# FET_M2.net
KiCad netlist of a schematic drawn in Altium Designer
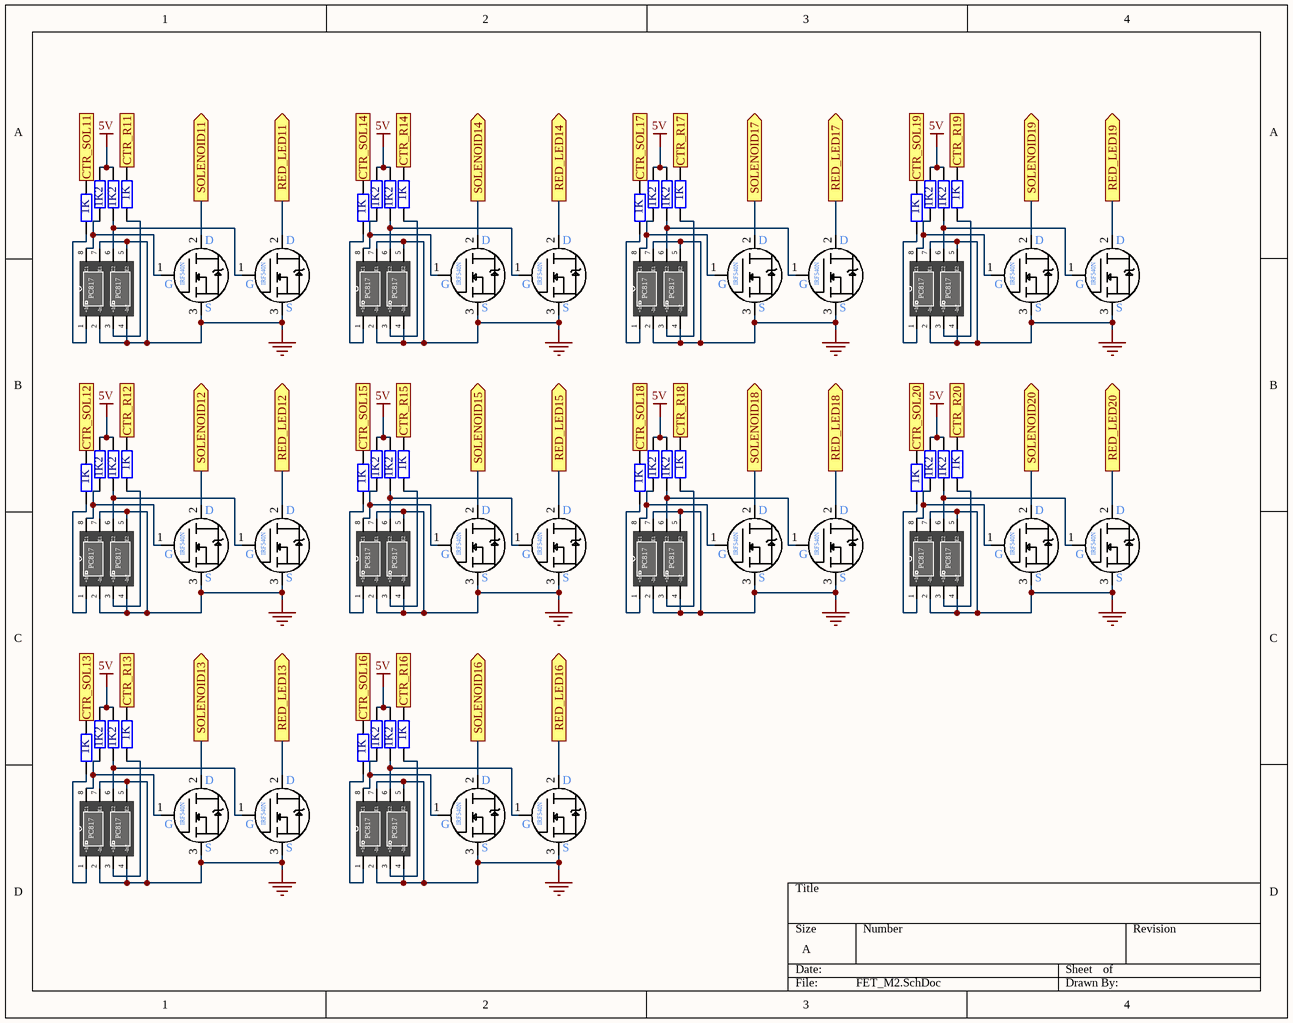
[diagram p0: FET_M2.SchDoc]

(export (version "E")
  (design (tool "Eeschema 10.0.6"))
  (components
    (comp (ref "FET21")
      (value "5#IRF540N")
      (footprint "5#IRF540N")
      (libsource (lib "Sch") (part "5#IRF540N"))
    )
    (comp (ref "FET22")
      (value "5#IRF540N")
      (footprint "5#IRF540N")
      (libsource (lib "Sch") (part "5#IRF540N"))
    )
    (comp (ref "FET23")
      (value "5#IRF540N")
      (footprint "5#IRF540N")
      (libsource (lib "Sch") (part "5#IRF540N"))
    )
    (comp (ref "FET24")
      (value "5#IRF540N")
      (footprint "5#IRF540N")
      (libsource (lib "Sch") (part "5#IRF540N"))
    )
    (comp (ref "FET25")
      (value "5#IRF540N")
      (footprint "5#IRF540N")
      (libsource (lib "Sch") (part "5#IRF540N"))
    )
    (comp (ref "FET26")
      (value "5#IRF540N")
      (footprint "5#IRF540N")
      (libsource (lib "Sch") (part "5#IRF540N"))
    )
    (comp (ref "FET27")
      (value "5#IRF540N")
      (footprint "5#IRF540N")
      (libsource (lib "Sch") (part "5#IRF540N"))
    )
    (comp (ref "FET28")
      (value "5#IRF540N")
      (footprint "5#IRF540N")
      (libsource (lib "Sch") (part "5#IRF540N"))
    )
    (comp (ref "FET29")
      (value "5#IRF540N")
      (footprint "5#IRF540N")
      (libsource (lib "Sch") (part "5#IRF540N"))
    )
    (comp (ref "FET30")
      (value "5#IRF540N")
      (footprint "5#IRF540N")
      (libsource (lib "Sch") (part "5#IRF540N"))
    )
    (comp (ref "FET31")
      (value "5#IRF540N")
      (footprint "5#IRF540N")
      (libsource (lib "Sch") (part "5#IRF540N"))
    )
    (comp (ref "FET32")
      (value "5#IRF540N")
      (footprint "5#IRF540N")
      (libsource (lib "Sch") (part "5#IRF540N"))
    )
    (comp (ref "FET33")
      (value "5#IRF540N")
      (footprint "5#IRF540N")
      (libsource (lib "Sch") (part "5#IRF540N"))
    )
    (comp (ref "FET34")
      (value "5#IRF540N")
      (footprint "5#IRF540N")
      (libsource (lib "Sch") (part "5#IRF540N"))
    )
    (comp (ref "FET35")
      (value "5#IRF540N")
      (footprint "5#IRF540N")
      (libsource (lib "Sch") (part "5#IRF540N"))
    )
    (comp (ref "FET36")
      (value "5#IRF540N")
      (footprint "5#IRF540N")
      (libsource (lib "Sch") (part "5#IRF540N"))
    )
    (comp (ref "FET37")
      (value "5#IRF540N")
      (footprint "5#IRF540N")
      (libsource (lib "Sch") (part "5#IRF540N"))
    )
    (comp (ref "FET38")
      (value "5#IRF540N")
      (footprint "5#IRF540N")
      (libsource (lib "Sch") (part "5#IRF540N"))
    )
    (comp (ref "FET39")
      (value "5#IRF540N")
      (footprint "5#IRF540N")
      (libsource (lib "Sch") (part "5#IRF540N"))
    )
    (comp (ref "FET40")
      (value "5#IRF540N")
      (footprint "5#IRF540N")
      (libsource (lib "Sch") (part "5#IRF540N"))
    )
    (comp (ref "PC11")
      (value "5#Dip8_PC817x2")
      (footprint "5#Dip8_PC817x2")
      (libsource (lib "Sch") (part "5#Dip8_PC817x2"))
    )
    (comp (ref "PC12")
      (value "5#Dip8_PC817x2")
      (footprint "5#Dip8_PC817x2")
      (libsource (lib "Sch") (part "5#Dip8_PC817x2"))
    )
    (comp (ref "PC13")
      (value "5#Dip8_PC817x2")
      (footprint "5#Dip8_PC817x2")
      (libsource (lib "Sch") (part "5#Dip8_PC817x2"))
    )
    (comp (ref "PC14")
      (value "5#Dip8_PC817x2")
      (footprint "5#Dip8_PC817x2")
      (libsource (lib "Sch") (part "5#Dip8_PC817x2"))
    )
    (comp (ref "PC15")
      (value "5#Dip8_PC817x2")
      (footprint "5#Dip8_PC817x2")
      (libsource (lib "Sch") (part "5#Dip8_PC817x2"))
    )
    (comp (ref "PC16")
      (value "5#Dip8_PC817x2")
      (footprint "5#Dip8_PC817x2")
      (libsource (lib "Sch") (part "5#Dip8_PC817x2"))
    )
    (comp (ref "PC17")
      (value "5#Dip8_PC817x2")
      (footprint "5#Dip8_PC817x2")
      (libsource (lib "Sch") (part "5#Dip8_PC817x2"))
    )
    (comp (ref "PC18")
      (value "5#Dip8_PC817x2")
      (footprint "5#Dip8_PC817x2")
      (libsource (lib "Sch") (part "5#Dip8_PC817x2"))
    )
    (comp (ref "PC19")
      (value "5#Dip8_PC817x2")
      (footprint "5#Dip8_PC817x2")
      (libsource (lib "Sch") (part "5#Dip8_PC817x2"))
    )
    (comp (ref "PC20")
      (value "5#Dip8_PC817x2")
      (footprint "5#Dip8_PC817x2")
      (libsource (lib "Sch") (part "5#Dip8_PC817x2"))
    )
    (comp (ref "R66")
      (value "1K2")
      (footprint "AXIAL-0.4")
      (description "Resistor")
      (fields (field (name "PUBLISHER") "Altium Limited"))
      (libsource (lib "Miscellaneous Devices") (part "Res2"))
    )
    (comp (ref "R67")
      (value "1K2")
      (footprint "AXIAL-0.4")
      (description "Resistor")
      (fields (field (name "PUBLISHER") "Altium Limited"))
      (libsource (lib "Miscellaneous Devices") (part "Res2"))
    )
    (comp (ref "R68")
      (value "1K")
      (footprint "AXIAL-0.4")
      (description "Resistor")
      (fields (field (name "PUBLISHER") "Altium Limited"))
      (libsource (lib "") (part "Res2_1"))
    )
    (comp (ref "R69")
      (value "1K2")
      (footprint "AXIAL-0.4")
      (description "Resistor")
      (fields (field (name "PUBLISHER") "Altium Limited"))
      (libsource (lib "Miscellaneous Devices") (part "Res2"))
    )
    (comp (ref "R70")
      (value "1K2")
      (footprint "AXIAL-0.4")
      (description "Resistor")
      (fields (field (name "PUBLISHER") "Altium Limited"))
      (libsource (lib "Miscellaneous Devices") (part "Res2"))
    )
    (comp (ref "R71")
      (value "1K")
      (footprint "AXIAL-0.4")
      (description "Resistor")
      (fields (field (name "PUBLISHER") "Altium Limited"))
      (libsource (lib "") (part "Res2_1"))
    )
    (comp (ref "R72")
      (value "1K2")
      (footprint "AXIAL-0.4")
      (description "Resistor")
      (fields (field (name "PUBLISHER") "Altium Limited"))
      (libsource (lib "Miscellaneous Devices") (part "Res2"))
    )
    (comp (ref "R73")
      (value "1K2")
      (footprint "AXIAL-0.4")
      (description "Resistor")
      (fields (field (name "PUBLISHER") "Altium Limited"))
      (libsource (lib "Miscellaneous Devices") (part "Res2"))
    )
    (comp (ref "R74")
      (value "1K")
      (footprint "AXIAL-0.4")
      (description "Resistor")
      (fields (field (name "PUBLISHER") "Altium Limited"))
      (libsource (lib "") (part "Res2_1"))
    )
    (comp (ref "R75")
      (value "1K2")
      (footprint "AXIAL-0.4")
      (description "Resistor")
      (fields (field (name "PUBLISHER") "Altium Limited"))
      (libsource (lib "Miscellaneous Devices") (part "Res2"))
    )
    (comp (ref "R76")
      (value "1K2")
      (footprint "AXIAL-0.4")
      (description "Resistor")
      (fields (field (name "PUBLISHER") "Altium Limited"))
      (libsource (lib "Miscellaneous Devices") (part "Res2"))
    )
    (comp (ref "R77")
      (value "1K")
      (footprint "AXIAL-0.4")
      (description "Resistor")
      (fields (field (name "PUBLISHER") "Altium Limited"))
      (libsource (lib "") (part "Res2_1"))
    )
    (comp (ref "R78")
      (value "1K")
      (footprint "AXIAL-0.4")
      (description "Resistor")
      (fields (field (name "PUBLISHER") "Altium Limited"))
      (libsource (lib "") (part "Res2_1"))
    )
    (comp (ref "R79")
      (value "1K")
      (footprint "AXIAL-0.4")
      (description "Resistor")
      (fields (field (name "PUBLISHER") "Altium Limited"))
      (libsource (lib "") (part "Res2_1"))
    )
    (comp (ref "R80")
      (value "1K")
      (footprint "AXIAL-0.4")
      (description "Resistor")
      (fields (field (name "PUBLISHER") "Altium Limited"))
      (libsource (lib "") (part "Res2_1"))
    )
    (comp (ref "R81")
      (value "1K")
      (footprint "AXIAL-0.4")
      (description "Resistor")
      (fields (field (name "PUBLISHER") "Altium Limited"))
      (libsource (lib "") (part "Res2_1"))
    )
    (comp (ref "R82")
      (value "1K2")
      (footprint "AXIAL-0.4")
      (description "Resistor")
      (fields (field (name "PUBLISHER") "Altium Limited"))
      (libsource (lib "Miscellaneous Devices") (part "Res2"))
    )
    (comp (ref "R83")
      (value "1K2")
      (footprint "AXIAL-0.4")
      (description "Resistor")
      (fields (field (name "PUBLISHER") "Altium Limited"))
      (libsource (lib "Miscellaneous Devices") (part "Res2"))
    )
    (comp (ref "R84")
      (value "1K")
      (footprint "AXIAL-0.4")
      (description "Resistor")
      (fields (field (name "PUBLISHER") "Altium Limited"))
      (libsource (lib "") (part "Res2_1"))
    )
    (comp (ref "R85")
      (value "1K2")
      (footprint "AXIAL-0.4")
      (description "Resistor")
      (fields (field (name "PUBLISHER") "Altium Limited"))
      (libsource (lib "Miscellaneous Devices") (part "Res2"))
    )
    (comp (ref "R86")
      (value "1K2")
      (footprint "AXIAL-0.4")
      (description "Resistor")
      (fields (field (name "PUBLISHER") "Altium Limited"))
      (libsource (lib "Miscellaneous Devices") (part "Res2"))
    )
    (comp (ref "R87")
      (value "1K")
      (footprint "AXIAL-0.4")
      (description "Resistor")
      (fields (field (name "PUBLISHER") "Altium Limited"))
      (libsource (lib "") (part "Res2_1"))
    )
    (comp (ref "R88")
      (value "1K2")
      (footprint "AXIAL-0.4")
      (description "Resistor")
      (fields (field (name "PUBLISHER") "Altium Limited"))
      (libsource (lib "Miscellaneous Devices") (part "Res2"))
    )
    (comp (ref "R89")
      (value "1K2")
      (footprint "AXIAL-0.4")
      (description "Resistor")
      (fields (field (name "PUBLISHER") "Altium Limited"))
      (libsource (lib "Miscellaneous Devices") (part "Res2"))
    )
    (comp (ref "R90")
      (value "1K")
      (footprint "AXIAL-0.4")
      (description "Resistor")
      (fields (field (name "PUBLISHER") "Altium Limited"))
      (libsource (lib "") (part "Res2_1"))
    )
    (comp (ref "R91")
      (value "1K2")
      (footprint "AXIAL-0.4")
      (description "Resistor")
      (fields (field (name "PUBLISHER") "Altium Limited"))
      (libsource (lib "Miscellaneous Devices") (part "Res2"))
    )
    (comp (ref "R92")
      (value "1K2")
      (footprint "AXIAL-0.4")
      (description "Resistor")
      (fields (field (name "PUBLISHER") "Altium Limited"))
      (libsource (lib "Miscellaneous Devices") (part "Res2"))
    )
    (comp (ref "R93")
      (value "1K")
      (footprint "AXIAL-0.4")
      (description "Resistor")
      (fields (field (name "PUBLISHER") "Altium Limited"))
      (libsource (lib "") (part "Res2_1"))
    )
    (comp (ref "R94")
      (value "1K")
      (footprint "AXIAL-0.4")
      (description "Resistor")
      (fields (field (name "PUBLISHER") "Altium Limited"))
      (libsource (lib "") (part "Res2_1"))
    )
    (comp (ref "R95")
      (value "1K")
      (footprint "AXIAL-0.4")
      (description "Resistor")
      (fields (field (name "PUBLISHER") "Altium Limited"))
      (libsource (lib "") (part "Res2_1"))
    )
    (comp (ref "R96")
      (value "1K")
      (footprint "AXIAL-0.4")
      (description "Resistor")
      (fields (field (name "PUBLISHER") "Altium Limited"))
      (libsource (lib "") (part "Res2_1"))
    )
    (comp (ref "R97")
      (value "1K")
      (footprint "AXIAL-0.4")
      (description "Resistor")
      (fields (field (name "PUBLISHER") "Altium Limited"))
      (libsource (lib "") (part "Res2_1"))
    )
    (comp (ref "R98")
      (value "1K2")
      (footprint "AXIAL-0.4")
      (description "Resistor")
      (fields (field (name "PUBLISHER") "Altium Limited"))
      (libsource (lib "Miscellaneous Devices") (part "Res2"))
    )
    (comp (ref "R99")
      (value "1K2")
      (footprint "AXIAL-0.4")
      (description "Resistor")
      (fields (field (name "PUBLISHER") "Altium Limited"))
      (libsource (lib "Miscellaneous Devices") (part "Res2"))
    )
    (comp (ref "R100")
      (value "1K")
      (footprint "AXIAL-0.4")
      (description "Resistor")
      (fields (field (name "PUBLISHER") "Altium Limited"))
      (libsource (lib "") (part "Res2_1"))
    )
    (comp (ref "R101")
      (value "1K2")
      (footprint "AXIAL-0.4")
      (description "Resistor")
      (fields (field (name "PUBLISHER") "Altium Limited"))
      (libsource (lib "Miscellaneous Devices") (part "Res2"))
    )
    (comp (ref "R102")
      (value "1K2")
      (footprint "AXIAL-0.4")
      (description "Resistor")
      (fields (field (name "PUBLISHER") "Altium Limited"))
      (libsource (lib "Miscellaneous Devices") (part "Res2"))
    )
    (comp (ref "R103")
      (value "1K")
      (footprint "AXIAL-0.4")
      (description "Resistor")
      (fields (field (name "PUBLISHER") "Altium Limited"))
      (libsource (lib "") (part "Res2_1"))
    )
    (comp (ref "R104")
      (value "1K")
      (footprint "AXIAL-0.4")
      (description "Resistor")
      (fields (field (name "PUBLISHER") "Altium Limited"))
      (libsource (lib "") (part "Res2_1"))
    )
    (comp (ref "R105")
      (value "1K")
      (footprint "AXIAL-0.4")
      (description "Resistor")
      (fields (field (name "PUBLISHER") "Altium Limited"))
      (libsource (lib "") (part "Res2_1"))
    )
  )
  (nets
    (net (code "1") (name "/CTR_R11") (class "Default")
      (node (ref "R68") (pin "1") (pinfunction "1_1") (pintype "passive"))
    )
    (net (code "2") (name "/CTR_R12") (class "Default")
      (node (ref "R84") (pin "1") (pinfunction "1_1") (pintype "passive"))
    )
    (net (code "3") (name "/CTR_R13") (class "Default")
      (node (ref "R100") (pin "1") (pinfunction "1_1") (pintype "passive"))
    )
    (net (code "4") (name "/CTR_R14") (class "Default")
      (node (ref "R71") (pin "1") (pinfunction "1_1") (pintype "passive"))
    )
    (net (code "5") (name "/CTR_R15") (class "Default")
      (node (ref "R87") (pin "1") (pinfunction "1_1") (pintype "passive"))
    )
    (net (code "6") (name "/CTR_R16") (class "Default")
      (node (ref "R103") (pin "1") (pinfunction "1_1") (pintype "passive"))
    )
    (net (code "7") (name "/CTR_R17") (class "Default")
      (node (ref "R74") (pin "1") (pinfunction "1_1") (pintype "passive"))
    )
    (net (code "8") (name "/CTR_R18") (class "Default")
      (node (ref "R90") (pin "1") (pinfunction "1_1") (pintype "passive"))
    )
    (net (code "9") (name "/CTR_R19") (class "Default")
      (node (ref "R77") (pin "1") (pinfunction "1_1") (pintype "passive"))
    )
    (net (code "10") (name "/CTR_R20") (class "Default")
      (node (ref "R93") (pin "1") (pinfunction "1_1") (pintype "passive"))
    )
    (net (code "11") (name "/CTR_SOL11") (class "Default")
      (node (ref "R78") (pin "1") (pinfunction "1_1") (pintype "passive"))
    )
    (net (code "12") (name "/CTR_SOL12") (class "Default")
      (node (ref "R94") (pin "1") (pinfunction "1_1") (pintype "passive"))
    )
    (net (code "13") (name "/CTR_SOL13") (class "Default")
      (node (ref "R104") (pin "1") (pinfunction "1_1") (pintype "passive"))
    )
    (net (code "14") (name "/CTR_SOL14") (class "Default")
      (node (ref "R79") (pin "1") (pinfunction "1_1") (pintype "passive"))
    )
    (net (code "15") (name "/CTR_SOL15") (class "Default")
      (node (ref "R95") (pin "1") (pinfunction "1_1") (pintype "passive"))
    )
    (net (code "16") (name "/CTR_SOL16") (class "Default")
      (node (ref "R105") (pin "1") (pinfunction "1_1") (pintype "passive"))
    )
    (net (code "17") (name "/CTR_SOL17") (class "Default")
      (node (ref "R80") (pin "1") (pinfunction "1_1") (pintype "passive"))
    )
    (net (code "18") (name "/CTR_SOL18") (class "Default")
      (node (ref "R96") (pin "1") (pinfunction "1_1") (pintype "passive"))
    )
    (net (code "19") (name "/CTR_SOL19") (class "Default")
      (node (ref "R81") (pin "1") (pinfunction "1_1") (pintype "passive"))
    )
    (net (code "20") (name "/CTR_SOL20") (class "Default")
      (node (ref "R97") (pin "1") (pinfunction "1_1") (pintype "passive"))
    )
    (net (code "21") (name "/RED_LED11") (class "Default")
      (node (ref "FET22") (pin "2") (pinfunction "D_2") (pintype "passive"))
    )
    (net (code "22") (name "/RED_LED12") (class "Default")
      (node (ref "FET30") (pin "2") (pinfunction "D_2") (pintype "passive"))
    )
    (net (code "23") (name "/RED_LED13") (class "Default")
      (node (ref "FET38") (pin "2") (pinfunction "D_2") (pintype "passive"))
    )
    (net (code "24") (name "/RED_LED14") (class "Default")
      (node (ref "FET24") (pin "2") (pinfunction "D_2") (pintype "passive"))
    )
    (net (code "25") (name "/RED_LED15") (class "Default")
      (node (ref "FET32") (pin "2") (pinfunction "D_2") (pintype "passive"))
    )
    (net (code "26") (name "/RED_LED16") (class "Default")
      (node (ref "FET40") (pin "2") (pinfunction "D_2") (pintype "passive"))
    )
    (net (code "27") (name "/RED_LED17") (class "Default")
      (node (ref "FET26") (pin "2") (pinfunction "D_2") (pintype "passive"))
    )
    (net (code "28") (name "/RED_LED18") (class "Default")
      (node (ref "FET34") (pin "2") (pinfunction "D_2") (pintype "passive"))
    )
    (net (code "29") (name "/RED_LED19") (class "Default")
      (node (ref "FET28") (pin "2") (pinfunction "D_2") (pintype "passive"))
    )
    (net (code "30") (name "/RED_LED20") (class "Default")
      (node (ref "FET36") (pin "2") (pinfunction "D_2") (pintype "passive"))
    )
    (net (code "31") (name "/SOLENOID11") (class "Default")
      (node (ref "FET21") (pin "2") (pinfunction "D_2") (pintype "passive"))
    )
    (net (code "32") (name "/SOLENOID12") (class "Default")
      (node (ref "FET29") (pin "2") (pinfunction "D_2") (pintype "passive"))
    )
    (net (code "33") (name "/SOLENOID13") (class "Default")
      (node (ref "FET37") (pin "2") (pinfunction "D_2") (pintype "passive"))
    )
    (net (code "34") (name "/SOLENOID14") (class "Default")
      (node (ref "FET23") (pin "2") (pinfunction "D_2") (pintype "passive"))
    )
    (net (code "35") (name "/SOLENOID15") (class "Default")
      (node (ref "FET31") (pin "2") (pinfunction "D_2") (pintype "passive"))
    )
    (net (code "36") (name "/SOLENOID16") (class "Default")
      (node (ref "FET39") (pin "2") (pinfunction "D_2") (pintype "passive"))
    )
    (net (code "37") (name "/SOLENOID17") (class "Default")
      (node (ref "FET25") (pin "2") (pinfunction "D_2") (pintype "passive"))
    )
    (net (code "38") (name "/SOLENOID18") (class "Default")
      (node (ref "FET33") (pin "2") (pinfunction "D_2") (pintype "passive"))
    )
    (net (code "39") (name "/SOLENOID19") (class "Default")
      (node (ref "FET27") (pin "2") (pinfunction "D_2") (pintype "passive"))
    )
    (net (code "40") (name "/SOLENOID20") (class "Default")
      (node (ref "FET35") (pin "2") (pinfunction "D_2") (pintype "passive"))
    )
    (net (code "41") (name "5V") (class "Default")
      (node (ref "R101") (pin "2") (pinfunction "2_2") (pintype "passive"))
      (node (ref "R102") (pin "2") (pinfunction "2_2") (pintype "passive"))
      (node (ref "R66") (pin "2") (pinfunction "2_2") (pintype "passive"))
      (node (ref "R67") (pin "2") (pinfunction "2_2") (pintype "passive"))
      (node (ref "R69") (pin "2") (pinfunction "2_2") (pintype "passive"))
      (node (ref "R70") (pin "2") (pinfunction "2_2") (pintype "passive"))
      (node (ref "R72") (pin "2") (pinfunction "2_2") (pintype "passive"))
      (node (ref "R73") (pin "2") (pinfunction "2_2") (pintype "passive"))
      (node (ref "R75") (pin "2") (pinfunction "2_2") (pintype "passive"))
      (node (ref "R76") (pin "2") (pinfunction "2_2") (pintype "passive"))
      (node (ref "R82") (pin "2") (pinfunction "2_2") (pintype "passive"))
      (node (ref "R83") (pin "2") (pinfunction "2_2") (pintype "passive"))
      (node (ref "R85") (pin "2") (pinfunction "2_2") (pintype "passive"))
      (node (ref "R86") (pin "2") (pinfunction "2_2") (pintype "passive"))
      (node (ref "R88") (pin "2") (pinfunction "2_2") (pintype "passive"))
      (node (ref "R89") (pin "2") (pinfunction "2_2") (pintype "passive"))
      (node (ref "R91") (pin "2") (pinfunction "2_2") (pintype "passive"))
      (node (ref "R92") (pin "2") (pinfunction "2_2") (pintype "passive"))
      (node (ref "R98") (pin "2") (pinfunction "2_2") (pintype "passive"))
      (node (ref "R99") (pin "2") (pinfunction "2_2") (pintype "passive"))
    )
    (net (code "42") (name "GND") (class "Default")
      (node (ref "FET21") (pin "3") (pinfunction "S_3") (pintype "passive"))
      (node (ref "FET22") (pin "3") (pinfunction "S_3") (pintype "passive"))
      (node (ref "FET23") (pin "3") (pinfunction "S_3") (pintype "passive"))
      (node (ref "FET24") (pin "3") (pinfunction "S_3") (pintype "passive"))
      (node (ref "FET25") (pin "3") (pinfunction "S_3") (pintype "passive"))
      (node (ref "FET26") (pin "3") (pinfunction "S_3") (pintype "passive"))
      (node (ref "FET27") (pin "3") (pinfunction "S_3") (pintype "passive"))
      (node (ref "FET28") (pin "3") (pinfunction "S_3") (pintype "passive"))
      (node (ref "FET29") (pin "3") (pinfunction "S_3") (pintype "passive"))
      (node (ref "FET30") (pin "3") (pinfunction "S_3") (pintype "passive"))
      (node (ref "FET31") (pin "3") (pinfunction "S_3") (pintype "passive"))
      (node (ref "FET32") (pin "3") (pinfunction "S_3") (pintype "passive"))
      (node (ref "FET33") (pin "3") (pinfunction "S_3") (pintype "passive"))
      (node (ref "FET34") (pin "3") (pinfunction "S_3") (pintype "passive"))
      (node (ref "FET35") (pin "3") (pinfunction "S_3") (pintype "passive"))
      (node (ref "FET36") (pin "3") (pinfunction "S_3") (pintype "passive"))
      (node (ref "FET37") (pin "3") (pinfunction "S_3") (pintype "passive"))
      (node (ref "FET38") (pin "3") (pinfunction "S_3") (pintype "passive"))
      (node (ref "FET39") (pin "3") (pinfunction "S_3") (pintype "passive"))
      (node (ref "FET40") (pin "3") (pinfunction "S_3") (pintype "passive"))
      (node (ref "PC11") (pin "2") (pinfunction "-In1_2") (pintype "passive"))
      (node (ref "PC11") (pin "4") (pinfunction "-In2_4") (pintype "passive"))
      (node (ref "PC11") (pin "5") (pinfunction "E2_5") (pintype "passive"))
      (node (ref "PC11") (pin "7") (pinfunction "E1_7") (pintype "passive"))
      (node (ref "PC12") (pin "2") (pinfunction "-In1_2") (pintype "passive"))
      (node (ref "PC12") (pin "4") (pinfunction "-In2_4") (pintype "passive"))
      (node (ref "PC12") (pin "5") (pinfunction "E2_5") (pintype "passive"))
      (node (ref "PC12") (pin "7") (pinfunction "E1_7") (pintype "passive"))
      (node (ref "PC13") (pin "2") (pinfunction "-In1_2") (pintype "passive"))
      (node (ref "PC13") (pin "4") (pinfunction "-In2_4") (pintype "passive"))
      (node (ref "PC13") (pin "5") (pinfunction "E2_5") (pintype "passive"))
      (node (ref "PC13") (pin "7") (pinfunction "E1_7") (pintype "passive"))
      (node (ref "PC14") (pin "2") (pinfunction "-In1_2") (pintype "passive"))
      (node (ref "PC14") (pin "4") (pinfunction "-In2_4") (pintype "passive"))
      (node (ref "PC14") (pin "5") (pinfunction "E2_5") (pintype "passive"))
      (node (ref "PC14") (pin "7") (pinfunction "E1_7") (pintype "passive"))
      (node (ref "PC15") (pin "2") (pinfunction "-In1_2") (pintype "passive"))
      (node (ref "PC15") (pin "4") (pinfunction "-In2_4") (pintype "passive"))
      (node (ref "PC15") (pin "5") (pinfunction "E2_5") (pintype "passive"))
      (node (ref "PC15") (pin "7") (pinfunction "E1_7") (pintype "passive"))
      (node (ref "PC16") (pin "2") (pinfunction "-In1_2") (pintype "passive"))
      (node (ref "PC16") (pin "4") (pinfunction "-In2_4") (pintype "passive"))
      (node (ref "PC16") (pin "5") (pinfunction "E2_5") (pintype "passive"))
      (node (ref "PC16") (pin "7") (pinfunction "E1_7") (pintype "passive"))
      (node (ref "PC17") (pin "2") (pinfunction "-In1_2") (pintype "passive"))
      (node (ref "PC17") (pin "4") (pinfunction "-In2_4") (pintype "passive"))
      (node (ref "PC17") (pin "5") (pinfunction "E2_5") (pintype "passive"))
      (node (ref "PC17") (pin "7") (pinfunction "E1_7") (pintype "passive"))
      (node (ref "PC18") (pin "2") (pinfunction "-In1_2") (pintype "passive"))
      (node (ref "PC18") (pin "4") (pinfunction "-In2_4") (pintype "passive"))
      (node (ref "PC18") (pin "5") (pinfunction "E2_5") (pintype "passive"))
      (node (ref "PC18") (pin "7") (pinfunction "E1_7") (pintype "passive"))
      (node (ref "PC19") (pin "2") (pinfunction "-In1_2") (pintype "passive"))
      (node (ref "PC19") (pin "4") (pinfunction "-In2_4") (pintype "passive"))
      (node (ref "PC19") (pin "5") (pinfunction "E2_5") (pintype "passive"))
      (node (ref "PC19") (pin "7") (pinfunction "E1_7") (pintype "passive"))
      (node (ref "PC20") (pin "2") (pinfunction "-In1_2") (pintype "passive"))
      (node (ref "PC20") (pin "4") (pinfunction "-In2_4") (pintype "passive"))
      (node (ref "PC20") (pin "5") (pinfunction "E2_5") (pintype "passive"))
      (node (ref "PC20") (pin "7") (pinfunction "E1_7") (pintype "passive"))
    )
    (net (code "43") (name "Net-(FET21-G)") (class "Default")
      (node (ref "FET21") (pin "1") (pinfunction "G_1") (pintype "passive"))
      (node (ref "PC11") (pin "8") (pinfunction "C1_8") (pintype "passive"))
      (node (ref "R66") (pin "1") (pinfunction "1_1") (pintype "passive"))
    )
    (net (code "44") (name "Net-(FET22-G)") (class "Default")
      (node (ref "FET22") (pin "1") (pinfunction "G_1") (pintype "passive"))
      (node (ref "PC11") (pin "6") (pinfunction "C2_6") (pintype "passive"))
      (node (ref "R67") (pin "1") (pinfunction "1_1") (pintype "passive"))
    )
    (net (code "45") (name "Net-(FET23-G)") (class "Default")
      (node (ref "FET23") (pin "1") (pinfunction "G_1") (pintype "passive"))
      (node (ref "PC12") (pin "8") (pinfunction "C1_8") (pintype "passive"))
      (node (ref "R69") (pin "1") (pinfunction "1_1") (pintype "passive"))
    )
    (net (code "46") (name "Net-(FET24-G)") (class "Default")
      (node (ref "FET24") (pin "1") (pinfunction "G_1") (pintype "passive"))
      (node (ref "PC12") (pin "6") (pinfunction "C2_6") (pintype "passive"))
      (node (ref "R70") (pin "1") (pinfunction "1_1") (pintype "passive"))
    )
    (net (code "47") (name "Net-(FET25-G)") (class "Default")
      (node (ref "FET25") (pin "1") (pinfunction "G_1") (pintype "passive"))
      (node (ref "PC13") (pin "8") (pinfunction "C1_8") (pintype "passive"))
      (node (ref "R72") (pin "1") (pinfunction "1_1") (pintype "passive"))
    )
    (net (code "48") (name "Net-(FET26-G)") (class "Default")
      (node (ref "FET26") (pin "1") (pinfunction "G_1") (pintype "passive"))
      (node (ref "PC13") (pin "6") (pinfunction "C2_6") (pintype "passive"))
      (node (ref "R73") (pin "1") (pinfunction "1_1") (pintype "passive"))
    )
    (net (code "49") (name "Net-(FET27-G)") (class "Default")
      (node (ref "FET27") (pin "1") (pinfunction "G_1") (pintype "passive"))
      (node (ref "PC14") (pin "8") (pinfunction "C1_8") (pintype "passive"))
      (node (ref "R75") (pin "1") (pinfunction "1_1") (pintype "passive"))
    )
    (net (code "50") (name "Net-(FET28-G)") (class "Default")
      (node (ref "FET28") (pin "1") (pinfunction "G_1") (pintype "passive"))
      (node (ref "PC14") (pin "6") (pinfunction "C2_6") (pintype "passive"))
      (node (ref "R76") (pin "1") (pinfunction "1_1") (pintype "passive"))
    )
    (net (code "51") (name "Net-(FET29-G)") (class "Default")
      (node (ref "FET29") (pin "1") (pinfunction "G_1") (pintype "passive"))
      (node (ref "PC15") (pin "8") (pinfunction "C1_8") (pintype "passive"))
      (node (ref "R82") (pin "1") (pinfunction "1_1") (pintype "passive"))
    )
    (net (code "52") (name "Net-(FET30-G)") (class "Default")
      (node (ref "FET30") (pin "1") (pinfunction "G_1") (pintype "passive"))
      (node (ref "PC15") (pin "6") (pinfunction "C2_6") (pintype "passive"))
      (node (ref "R83") (pin "1") (pinfunction "1_1") (pintype "passive"))
    )
    (net (code "53") (name "Net-(FET31-G)") (class "Default")
      (node (ref "FET31") (pin "1") (pinfunction "G_1") (pintype "passive"))
      (node (ref "PC16") (pin "8") (pinfunction "C1_8") (pintype "passive"))
      (node (ref "R85") (pin "1") (pinfunction "1_1") (pintype "passive"))
    )
    (net (code "54") (name "Net-(FET32-G)") (class "Default")
      (node (ref "FET32") (pin "1") (pinfunction "G_1") (pintype "passive"))
      (node (ref "PC16") (pin "6") (pinfunction "C2_6") (pintype "passive"))
      (node (ref "R86") (pin "1") (pinfunction "1_1") (pintype "passive"))
    )
    (net (code "55") (name "Net-(FET33-G)") (class "Default")
      (node (ref "FET33") (pin "1") (pinfunction "G_1") (pintype "passive"))
      (node (ref "PC17") (pin "8") (pinfunction "C1_8") (pintype "passive"))
      (node (ref "R88") (pin "1") (pinfunction "1_1") (pintype "passive"))
    )
    (net (code "56") (name "Net-(FET34-G)") (class "Default")
      (node (ref "FET34") (pin "1") (pinfunction "G_1") (pintype "passive"))
      (node (ref "PC17") (pin "6") (pinfunction "C2_6") (pintype "passive"))
      (node (ref "R89") (pin "1") (pinfunction "1_1") (pintype "passive"))
    )
    (net (code "57") (name "Net-(FET35-G)") (class "Default")
      (node (ref "FET35") (pin "1") (pinfunction "G_1") (pintype "passive"))
      (node (ref "PC18") (pin "8") (pinfunction "C1_8") (pintype "passive"))
      (node (ref "R91") (pin "1") (pinfunction "1_1") (pintype "passive"))
    )
    (net (code "58") (name "Net-(FET36-G)") (class "Default")
      (node (ref "FET36") (pin "1") (pinfunction "G_1") (pintype "passive"))
      (node (ref "PC18") (pin "6") (pinfunction "C2_6") (pintype "passive"))
      (node (ref "R92") (pin "1") (pinfunction "1_1") (pintype "passive"))
    )
    (net (code "59") (name "Net-(FET37-G)") (class "Default")
      (node (ref "FET37") (pin "1") (pinfunction "G_1") (pintype "passive"))
      (node (ref "PC19") (pin "8") (pinfunction "C1_8") (pintype "passive"))
      (node (ref "R98") (pin "1") (pinfunction "1_1") (pintype "passive"))
    )
    (net (code "60") (name "Net-(FET38-G)") (class "Default")
      (node (ref "FET38") (pin "1") (pinfunction "G_1") (pintype "passive"))
      (node (ref "PC19") (pin "6") (pinfunction "C2_6") (pintype "passive"))
      (node (ref "R99") (pin "1") (pinfunction "1_1") (pintype "passive"))
    )
    (net (code "61") (name "Net-(FET39-G)") (class "Default")
      (node (ref "FET39") (pin "1") (pinfunction "G_1") (pintype "passive"))
      (node (ref "PC20") (pin "8") (pinfunction "C1_8") (pintype "passive"))
      (node (ref "R101") (pin "1") (pinfunction "1_1") (pintype "passive"))
    )
    (net (code "62") (name "Net-(FET40-G)") (class "Default")
      (node (ref "FET40") (pin "1") (pinfunction "G_1") (pintype "passive"))
      (node (ref "PC20") (pin "6") (pinfunction "C2_6") (pintype "passive"))
      (node (ref "R102") (pin "1") (pinfunction "1_1") (pintype "passive"))
    )
    (net (code "63") (name "Net-(PC11-+In1)") (class "Default")
      (node (ref "PC11") (pin "1") (pinfunction "+In1_1") (pintype "passive"))
      (node (ref "R78") (pin "2") (pinfunction "2_2") (pintype "passive"))
    )
    (net (code "64") (name "Net-(PC11-+In2)") (class "Default")
      (node (ref "PC11") (pin "3") (pinfunction "+In2_3") (pintype "passive"))
      (node (ref "R68") (pin "2") (pinfunction "2_2") (pintype "passive"))
    )
    (net (code "65") (name "Net-(PC12-+In1)") (class "Default")
      (node (ref "PC12") (pin "1") (pinfunction "+In1_1") (pintype "passive"))
      (node (ref "R79") (pin "2") (pinfunction "2_2") (pintype "passive"))
    )
    (net (code "66") (name "Net-(PC12-+In2)") (class "Default")
      (node (ref "PC12") (pin "3") (pinfunction "+In2_3") (pintype "passive"))
      (node (ref "R71") (pin "2") (pinfunction "2_2") (pintype "passive"))
    )
    (net (code "67") (name "Net-(PC13-+In1)") (class "Default")
      (node (ref "PC13") (pin "1") (pinfunction "+In1_1") (pintype "passive"))
      (node (ref "R80") (pin "2") (pinfunction "2_2") (pintype "passive"))
    )
    (net (code "68") (name "Net-(PC13-+In2)") (class "Default")
      (node (ref "PC13") (pin "3") (pinfunction "+In2_3") (pintype "passive"))
      (node (ref "R74") (pin "2") (pinfunction "2_2") (pintype "passive"))
    )
    (net (code "69") (name "Net-(PC14-+In1)") (class "Default")
      (node (ref "PC14") (pin "1") (pinfunction "+In1_1") (pintype "passive"))
      (node (ref "R81") (pin "2") (pinfunction "2_2") (pintype "passive"))
    )
    (net (code "70") (name "Net-(PC14-+In2)") (class "Default")
      (node (ref "PC14") (pin "3") (pinfunction "+In2_3") (pintype "passive"))
      (node (ref "R77") (pin "2") (pinfunction "2_2") (pintype "passive"))
    )
    (net (code "71") (name "Net-(PC15-+In1)") (class "Default")
      (node (ref "PC15") (pin "1") (pinfunction "+In1_1") (pintype "passive"))
      (node (ref "R94") (pin "2") (pinfunction "2_2") (pintype "passive"))
    )
    (net (code "72") (name "Net-(PC15-+In2)") (class "Default")
      (node (ref "PC15") (pin "3") (pinfunction "+In2_3") (pintype "passive"))
      (node (ref "R84") (pin "2") (pinfunction "2_2") (pintype "passive"))
    )
    (net (code "73") (name "Net-(PC16-+In1)") (class "Default")
      (node (ref "PC16") (pin "1") (pinfunction "+In1_1") (pintype "passive"))
      (node (ref "R95") (pin "2") (pinfunction "2_2") (pintype "passive"))
    )
    (net (code "74") (name "Net-(PC16-+In2)") (class "Default")
      (node (ref "PC16") (pin "3") (pinfunction "+In2_3") (pintype "passive"))
      (node (ref "R87") (pin "2") (pinfunction "2_2") (pintype "passive"))
    )
    (net (code "75") (name "Net-(PC17-+In1)") (class "Default")
      (node (ref "PC17") (pin "1") (pinfunction "+In1_1") (pintype "passive"))
      (node (ref "R96") (pin "2") (pinfunction "2_2") (pintype "passive"))
    )
    (net (code "76") (name "Net-(PC17-+In2)") (class "Default")
      (node (ref "PC17") (pin "3") (pinfunction "+In2_3") (pintype "passive"))
      (node (ref "R90") (pin "2") (pinfunction "2_2") (pintype "passive"))
    )
    (net (code "77") (name "Net-(PC18-+In1)") (class "Default")
      (node (ref "PC18") (pin "1") (pinfunction "+In1_1") (pintype "passive"))
      (node (ref "R97") (pin "2") (pinfunction "2_2") (pintype "passive"))
    )
    (net (code "78") (name "Net-(PC18-+In2)") (class "Default")
      (node (ref "PC18") (pin "3") (pinfunction "+In2_3") (pintype "passive"))
      (node (ref "R93") (pin "2") (pinfunction "2_2") (pintype "passive"))
    )
    (net (code "79") (name "Net-(PC19-+In1)") (class "Default")
      (node (ref "PC19") (pin "1") (pinfunction "+In1_1") (pintype "passive"))
      (node (ref "R104") (pin "2") (pinfunction "2_2") (pintype "passive"))
    )
    (net (code "80") (name "Net-(PC19-+In2)") (class "Default")
      (node (ref "PC19") (pin "3") (pinfunction "+In2_3") (pintype "passive"))
      (node (ref "R100") (pin "2") (pinfunction "2_2") (pintype "passive"))
    )
    (net (code "81") (name "Net-(PC20-+In1)") (class "Default")
      (node (ref "PC20") (pin "1") (pinfunction "+In1_1") (pintype "passive"))
      (node (ref "R105") (pin "2") (pinfunction "2_2") (pintype "passive"))
    )
    (net (code "82") (name "Net-(PC20-+In2)") (class "Default")
      (node (ref "PC20") (pin "3") (pinfunction "+In2_3") (pintype "passive"))
      (node (ref "R103") (pin "2") (pinfunction "2_2") (pintype "passive"))
    )
  )
)
